# Shield.net
KiCad netlist of a schematic drawn in EAGLE
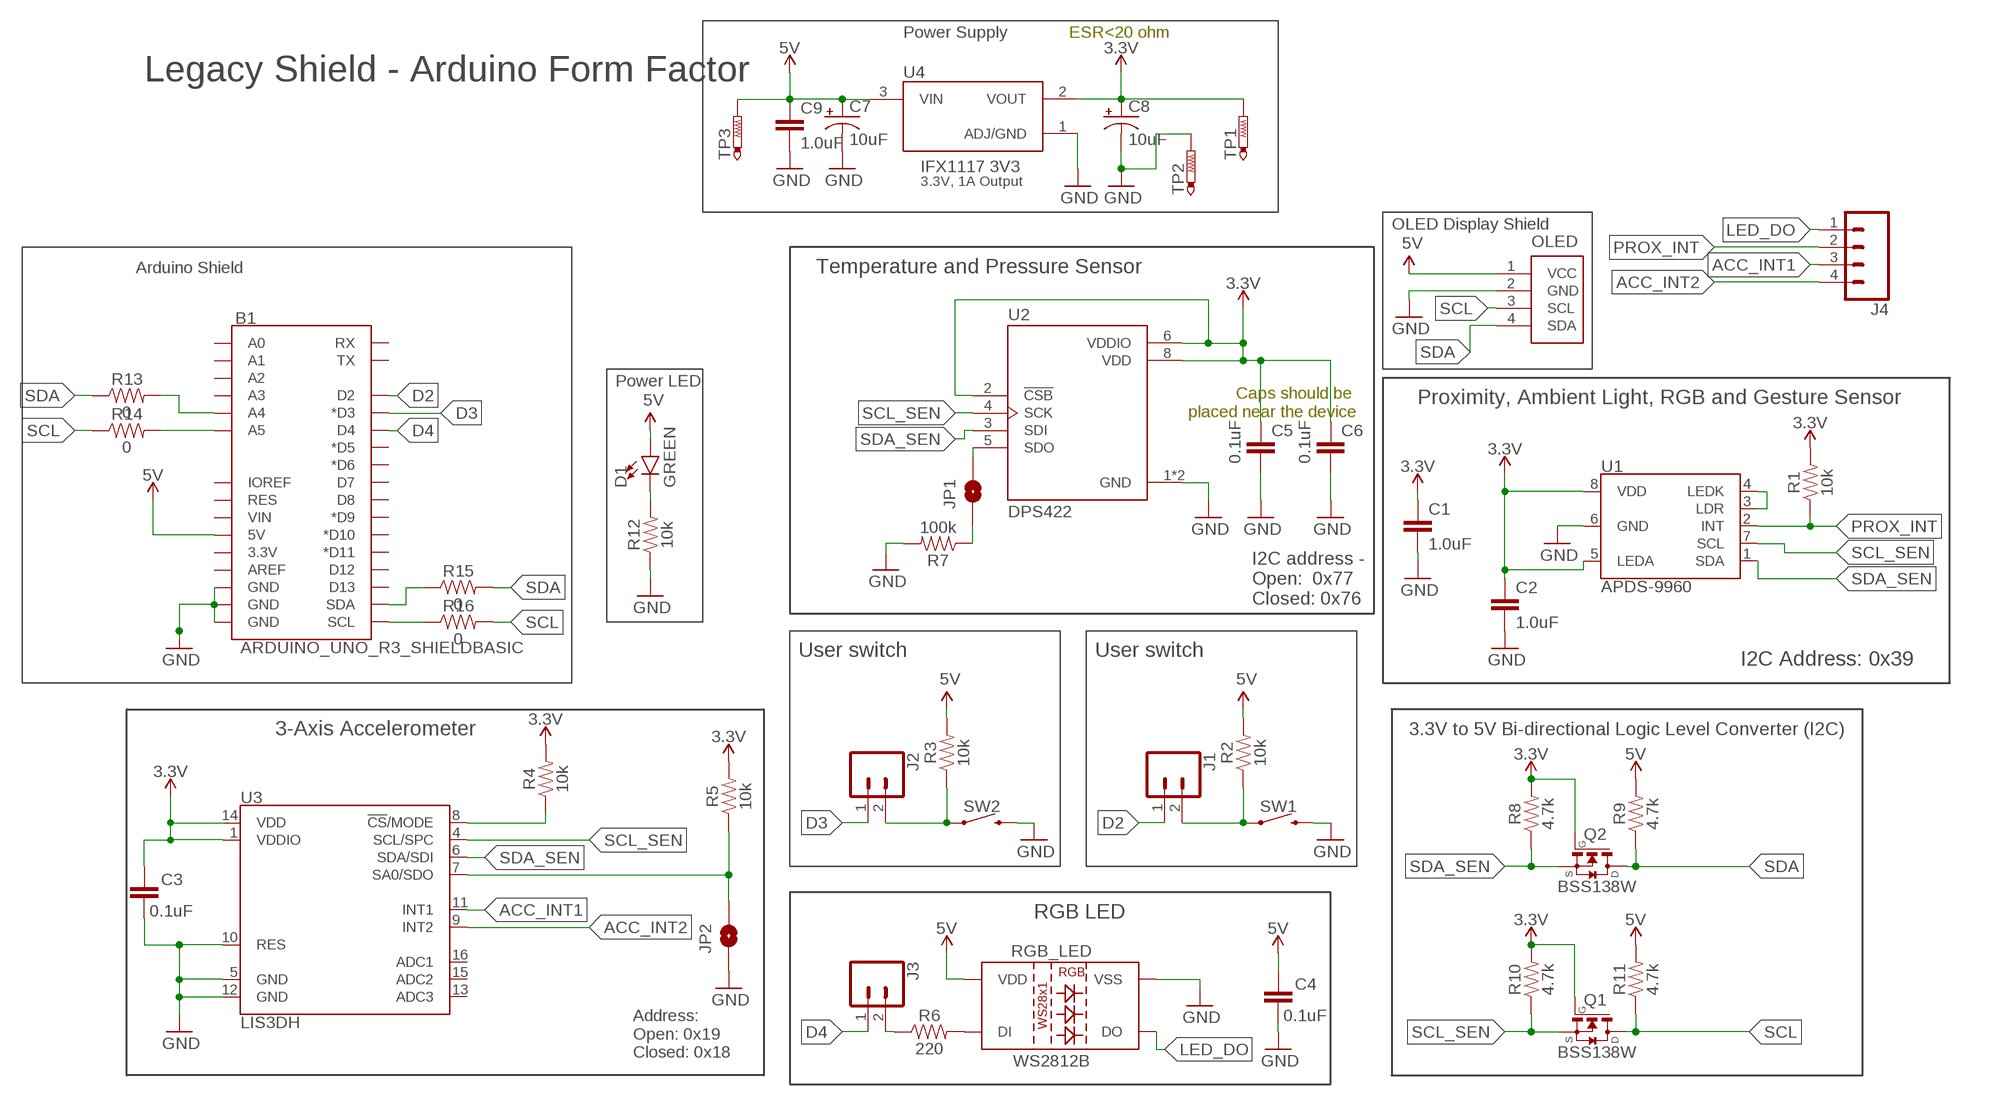
[diagram p0: schematic, sheet 1]

(export (version "E")
  (design (tool "Eeschema 10.0.6"))
  (components
    (comp (ref "B1")
      (value "ARDUINO_UNO_R3_SHIELDBASIC")
      (footprint "eagle-import:UNO_R3_SHIELD")
      (libsource (lib "eagle-import") (part "ARDUINO_UNO_R3_SHIELDBASIC"))
    )
    (comp (ref "C1")
      (value "1.0uF")
      (footprint "eagle-import:0603-CAP")
      (libsource (lib "eagle-import") (part "1.0UF-16V-10%(0603)"))
    )
    (comp (ref "C2")
      (value "1.0uF")
      (footprint "eagle-import:0603-CAP")
      (libsource (lib "eagle-import") (part "1.0UF-16V-10%(0603)"))
    )
    (comp (ref "C3")
      (value "0.1uF")
      (footprint "eagle-import:0603")
      (libsource (lib "eagle-import") (part "0.1UF-0603-25V-(+80/-20%)"))
    )
    (comp (ref "C4")
      (value "0.1uF")
      (footprint "eagle-import:0603")
      (libsource (lib "eagle-import") (part "0.1UF-0603-25V-(+80/-20%)"))
    )
    (comp (ref "C5")
      (value "0.1uF")
      (footprint "eagle-import:0603")
      (libsource (lib "eagle-import") (part "0.1UF-0603-25V-(+80/-20%)"))
    )
    (comp (ref "C6")
      (value "0.1uF")
      (footprint "eagle-import:0603")
      (libsource (lib "eagle-import") (part "0.1UF-0603-25V-(+80/-20%)"))
    )
    (comp (ref "C7")
      (value "10uF")
      (footprint "eagle-import:EIA3528")
      (libsource (lib "eagle-import") (part "10UF-POLAR-EIA3528-20V-10%(TANT)"))
    )
    (comp (ref "C8")
      (value "10uF")
      (footprint "eagle-import:EIA3528")
      (libsource (lib "eagle-import") (part "10UF-POLAR-EIA3528-20V-10%(TANT)"))
    )
    (comp (ref "C9")
      (value "1.0uF")
      (footprint "eagle-import:0603-CAP")
      (libsource (lib "eagle-import") (part "1.0UF-16V-10%(0603)"))
    )
    (comp (ref "D1")
      (value "GREEN")
      (footprint "eagle-import:LED-1206")
      (libsource (lib "eagle-import") (part "LED-GREEN1206"))
    )
    (comp (ref "J1")
      (value "CONN_02")
      (footprint "eagle-import:1X02")
      (libsource (lib "eagle-import") (part "CONN_02"))
    )
    (comp (ref "J2")
      (value "CONN_02")
      (footprint "eagle-import:1X02")
      (libsource (lib "eagle-import") (part "CONN_02"))
    )
    (comp (ref "J3")
      (value "CONN_02")
      (footprint "eagle-import:1X02")
      (libsource (lib "eagle-import") (part "CONN_02"))
    )
    (comp (ref "J4")
      (value "CONN_04")
      (footprint "eagle-import:1X04")
      (libsource (lib "eagle-import") (part "CONN_04"))
    )
    (comp (ref "JP1")
      (value "JUMPER-SMT_2_NO_SILK")
      (footprint "eagle-import:SMT-JUMPER_2_NO_SILK")
      (libsource (lib "eagle-import") (part "JUMPER-SMT_2_NO_SILK"))
    )
    (comp (ref "JP2")
      (value "JUMPER-SMT_2_NO_SILK")
      (footprint "eagle-import:SMT-JUMPER_2_NO_SILK")
      (libsource (lib "eagle-import") (part "JUMPER-SMT_2_NO_SILK"))
    )
    (comp (ref "OLED")
      (value "OLED_4_PIN")
      (footprint "eagle-import:OLED_4PIN")
      (description "0.96 Inch I2C/IIC 4pin OLED Display Module")
      (fields (field (name "MF") "Adafruit Industries"))
      (libsource (lib "eagle-import") (part "OLED_4_PIN"))
    )
    (comp (ref "Q1")
      (value "BSS138W")
      (footprint "eagle-import:SOT323-R")
      (description "N-Channel 60V 280mA (Ta) 500mW (Ta) Surface Mount PG-SOT323-3")
      (fields
        (field (name "DIGI-KEY_PART_NUMBER") "BSS138WCT-ND")
        (field (name "MF") "ON Semiconductor")
        (field (name "DIGI-KEY_PART_NUMBER_1") "BSS138WH6327XTSA1CT-ND")
        (field (name "DIGI-KEY_PURCHASE_URL") "https://www.digikey.in/product-detail/en/infineon-technologies/BSS138WH6327XTSA1/BSS138WH6327XTSA1CT-ND/5410000")
        (field (name "MF_1") "Infineon Technologies")
        (field (name "PACKAGE") "SOT-323")
      )
      (libsource (lib "eagle-import") (part "BSS138W"))
    )
    (comp (ref "Q2")
      (value "BSS138W")
      (footprint "eagle-import:SOT323-R")
      (description "N-Channel 60V 280mA (Ta) 500mW (Ta) Surface Mount PG-SOT323-3")
      (fields
        (field (name "DIGI-KEY_PART_NUMBER") "BSS138WCT-ND")
        (field (name "MF") "ON Semiconductor")
        (field (name "DIGI-KEY_PART_NUMBER_1") "BSS138WH6327XTSA1CT-ND")
        (field (name "DIGI-KEY_PURCHASE_URL") "https://www.digikey.in/product-detail/en/infineon-technologies/BSS138WH6327XTSA1/BSS138WH6327XTSA1CT-ND/5410000")
        (field (name "MF_1") "Infineon Technologies")
        (field (name "PACKAGE") "SOT-323")
      )
      (libsource (lib "eagle-import") (part "BSS138W"))
    )
    (comp (ref "R1")
      (value "10k")
      (footprint "eagle-import:0603")
      (libsource (lib "eagle-import") (part "10KOHM-0603-1/10W-1%"))
    )
    (comp (ref "R2")
      (value "10k")
      (footprint "eagle-import:0603")
      (libsource (lib "eagle-import") (part "10KOHM-0603-1/10W-1%"))
    )
    (comp (ref "R3")
      (value "10k")
      (footprint "eagle-import:0603")
      (libsource (lib "eagle-import") (part "10KOHM-0603-1/10W-1%"))
    )
    (comp (ref "R4")
      (value "10k")
      (footprint "eagle-import:0603")
      (libsource (lib "eagle-import") (part "10KOHM-0603-1/10W-1%"))
    )
    (comp (ref "R5")
      (value "10k")
      (footprint "eagle-import:0603")
      (libsource (lib "eagle-import") (part "10KOHM-0603-1/10W-1%"))
    )
    (comp (ref "R6")
      (value "220")
      (footprint "eagle-import:0603")
      (libsource (lib "eagle-import") (part "220OHM-0603-1/10W-1%"))
    )
    (comp (ref "R7")
      (value "100k")
      (footprint "eagle-import:0603")
      (libsource (lib "eagle-import") (part "100KOHM-0603-1/10W-1%"))
    )
    (comp (ref "R8")
      (value "4.7k")
      (footprint "eagle-import:0603")
      (libsource (lib "eagle-import") (part "4.7KOHM-0603-1/10W-1%"))
    )
    (comp (ref "R9")
      (value "4.7k")
      (footprint "eagle-import:0603")
      (libsource (lib "eagle-import") (part "4.7KOHM-0603-1/10W-1%"))
    )
    (comp (ref "R10")
      (value "4.7k")
      (footprint "eagle-import:0603")
      (libsource (lib "eagle-import") (part "4.7KOHM-0603-1/10W-1%"))
    )
    (comp (ref "R11")
      (value "4.7k")
      (footprint "eagle-import:0603")
      (libsource (lib "eagle-import") (part "4.7KOHM-0603-1/10W-1%"))
    )
    (comp (ref "R12")
      (value "10k")
      (footprint "eagle-import:0603")
      (libsource (lib "eagle-import") (part "10KOHM-0603-1/10W-1%"))
    )
    (comp (ref "R13")
      (value "0")
      (footprint "eagle-import:0603")
      (libsource (lib "eagle-import") (part "0OHM-0603-1/10W-5%"))
    )
    (comp (ref "R14")
      (value "0")
      (footprint "eagle-import:0603")
      (libsource (lib "eagle-import") (part "0OHM-0603-1/10W-5%"))
    )
    (comp (ref "R15")
      (value "0")
      (footprint "eagle-import:0603")
      (libsource (lib "eagle-import") (part "0OHM-0603-1/10W-5%"))
    )
    (comp (ref "R16")
      (value "0")
      (footprint "eagle-import:0603")
      (libsource (lib "eagle-import") (part "0OHM-0603-1/10W-5%"))
    )
    (comp (ref "RGB_LED")
      (value "WS2812B")
      (footprint "eagle-import:WS2812B")
      (libsource (lib "eagle-import") (part "WS2812B"))
    )
    (comp (ref "SW1")
      (value "MOMENTARY-SWITCH-SPST-PTH-6.0MM")
      (footprint "eagle-import:TACTILE_SWITCH_PTH_6.0MM")
      (libsource (lib "eagle-import") (part "MOMENTARY-SWITCH-SPST-PTH-6.0MM"))
    )
    (comp (ref "SW2")
      (value "MOMENTARY-SWITCH-SPST-PTH-6.0MM")
      (footprint "eagle-import:TACTILE_SWITCH_PTH_6.0MM")
      (libsource (lib "eagle-import") (part "MOMENTARY-SWITCH-SPST-PTH-6.0MM"))
    )
    (comp (ref "TP1")
      (value "PTR1TP08R")
      (footprint "eagle-import:TP08R")
      (libsource (lib "eagle-import") (part "PTR1TP08R"))
    )
    (comp (ref "TP2")
      (value "PTR1TP08R")
      (footprint "eagle-import:TP08R")
      (libsource (lib "eagle-import") (part "PTR1TP08R"))
    )
    (comp (ref "TP3")
      (value "PTR1TP08R")
      (footprint "eagle-import:TP08R")
      (libsource (lib "eagle-import") (part "PTR1TP08R"))
    )
    (comp (ref "U1")
      (value "APDS-9960")
      (footprint "eagle-import:APDS-9960")
      (fields (field (name "MF") "Broadcom Limited") (field (name "DIGI-KEY_PART_NUMBER") "516-3480-1-ND"))
      (libsource (lib "eagle-import") (part "APDS-9960"))
    )
    (comp (ref "U2")
      (value "DPS422")
      (footprint "eagle-import:XDCR_DPS422")
      (fields
        (field (name "MF") "Infineon Technologies")
        (field (name "DIGI-KEY_PART_NUMBER") "DPS422XTSA1CT-ND")
      )
      (libsource (lib "eagle-import") (part "DPS422"))
    )
    (comp (ref "U3")
      (value "LIS3DH")
      (footprint "eagle-import:LGA-16-3X3")
      (libsource (lib "eagle-import") (part "LIS3DH"))
    )
    (comp (ref "U4")
      (value "IFX1117 3V3")
      (footprint "eagle-import:SOT229P700X180-4N")
      (description "IC REG LINEAR 3.3V 1A SOT223-4")
      (fields
        (field (name "MF") "Advanced Monolithic Systems")
        (field (name "MP") "AMS1117-3.3")
        (field (name "DIGI-KEY_PART_NUMBER") "IFX1117MEV33HTMA1CT-ND")
        (field (name "MF_1") "Infineon Technologies")
        (field (name "MP_1") "IFX1117")
        (field (name "PACKAGE") "SOT223-4")
      )
      (libsource (lib "eagle-import") (part "AMS1117-3.3"))
    )
  )
  (nets
    (net (code "1") (name "3.3V") (class "Default")
      (node (ref "C1") (pin "1") (pinfunction "1_1") (pintype "passive"))
      (node (ref "C2") (pin "1") (pinfunction "1_1") (pintype "passive"))
      (node (ref "C3") (pin "1") (pinfunction "1_1") (pintype "passive"))
      (node (ref "C5") (pin "1") (pinfunction "1_1") (pintype "passive"))
      (node (ref "C6") (pin "1") (pinfunction "1_1") (pintype "passive"))
      (node (ref "C8") (pin "A") (pinfunction "+_A") (pintype "passive"))
      (node (ref "Q1") (pin "1") (pinfunction "G_1") (pintype "passive"))
      (node (ref "Q2") (pin "1") (pinfunction "G_1") (pintype "passive"))
      (node (ref "R1") (pin "2") (pinfunction "2_2") (pintype "passive"))
      (node (ref "R10") (pin "2") (pinfunction "2_2") (pintype "passive"))
      (node (ref "R4") (pin "2") (pinfunction "2_2") (pintype "passive"))
      (node (ref "R5") (pin "2") (pinfunction "2_2") (pintype "passive"))
      (node (ref "R8") (pin "2") (pinfunction "2_2") (pintype "passive"))
      (node (ref "TP1") (pin "TP") (pinfunction "TP_TP") (pintype "input"))
      (node (ref "U1") (pin "5") (pinfunction "LEDA_5") (pintype "bidirectional"))
      (node (ref "U1") (pin "8") (pinfunction "VDD_8") (pintype "bidirectional"))
      (node (ref "U2") (pin "2") (pinfunction "~{CSB}_2") (pintype "input"))
      (node (ref "U2") (pin "6") (pinfunction "VDDIO_6") (pintype "power_in"))
      (node (ref "U2") (pin "8") (pinfunction "VDD_8") (pintype "power_in"))
      (node (ref "U3") (pin "1") (pinfunction "VDDIO_1") (pintype "bidirectional"))
      (node (ref "U3") (pin "14") (pinfunction "VDD_14") (pintype "bidirectional"))
      (node (ref "U4") (pin "2") (pinfunction "VOUT_2") (pintype "output"))
    )
    (net (code "2") (name "5V") (class "Default")
      (node (ref "B1") (pin "5V") (pinfunction "5V_5V") (pintype "bidirectional"))
      (node (ref "C4") (pin "1") (pinfunction "1_1") (pintype "passive"))
      (node (ref "C7") (pin "A") (pinfunction "+_A") (pintype "passive"))
      (node (ref "C9") (pin "1") (pinfunction "1_1") (pintype "passive"))
      (node (ref "D1") (pin "A") (pinfunction "A_A") (pintype "passive"))
      (node (ref "OLED") (pin "1") (pinfunction "VCC_1") (pintype "bidirectional"))
      (node (ref "R11") (pin "2") (pinfunction "2_2") (pintype "passive"))
      (node (ref "R2") (pin "2") (pinfunction "2_2") (pintype "passive"))
      (node (ref "R3") (pin "2") (pinfunction "2_2") (pintype "passive"))
      (node (ref "R9") (pin "2") (pinfunction "2_2") (pintype "passive"))
      (node (ref "RGB_LED") (pin "1") (pinfunction "VDD_1") (pintype "bidirectional"))
      (node (ref "TP3") (pin "TP") (pinfunction "TP_TP") (pintype "input"))
      (node (ref "U4") (pin "3") (pinfunction "VIN_3") (pintype "input"))
    )
    (net (code "3") (name "ACC_INT1") (class "Default")
      (node (ref "J4") (pin "3") (pinfunction "3_3") (pintype "passive"))
      (node (ref "U3") (pin "11") (pinfunction "INT1_11") (pintype "bidirectional"))
    )
    (net (code "4") (name "ACC_INT2") (class "Default")
      (node (ref "J4") (pin "4") (pinfunction "4_4") (pintype "passive"))
      (node (ref "U3") (pin "9") (pinfunction "INT2_9") (pintype "bidirectional"))
    )
    (net (code "5") (name "D2") (class "Default")
      (node (ref "B1") (pin "D2") (pinfunction "D2_D2") (pintype "bidirectional"))
      (node (ref "J1") (pin "1") (pinfunction "1_1") (pintype "passive"))
    )
    (net (code "6") (name "D3") (class "Default")
      (node (ref "B1") (pin "D3") (pinfunction "*D3_D3") (pintype "bidirectional"))
      (node (ref "J2") (pin "1") (pinfunction "1_1") (pintype "passive"))
    )
    (net (code "7") (name "D4") (class "Default")
      (node (ref "B1") (pin "D4") (pinfunction "D4_D4") (pintype "bidirectional"))
      (node (ref "J3") (pin "1") (pinfunction "1_1") (pintype "passive"))
    )
    (net (code "8") (name "GND") (class "Default")
      (node (ref "B1") (pin "GND@0") (pinfunction "GND_GND@0") (pintype "bidirectional"))
      (node (ref "B1") (pin "GND@1") (pinfunction "GND_GND@1") (pintype "bidirectional"))
      (node (ref "B1") (pin "GND@2") (pinfunction "GND_GND@2") (pintype "bidirectional"))
      (node (ref "C1") (pin "2") (pinfunction "2_2") (pintype "passive"))
      (node (ref "C2") (pin "2") (pinfunction "2_2") (pintype "passive"))
      (node (ref "C3") (pin "2") (pinfunction "2_2") (pintype "passive"))
      (node (ref "C4") (pin "2") (pinfunction "2_2") (pintype "passive"))
      (node (ref "C5") (pin "2") (pinfunction "2_2") (pintype "passive"))
      (node (ref "C6") (pin "2") (pinfunction "2_2") (pintype "passive"))
      (node (ref "C7") (pin "C") (pinfunction "-_C") (pintype "passive"))
      (node (ref "C8") (pin "C") (pinfunction "-_C") (pintype "passive"))
      (node (ref "C9") (pin "2") (pinfunction "2_2") (pintype "passive"))
      (node (ref "JP2") (pin "1") (pinfunction "1_1") (pintype "passive"))
      (node (ref "OLED") (pin "2") (pinfunction "GND_2") (pintype "bidirectional"))
      (node (ref "R12") (pin "1") (pinfunction "1_1") (pintype "passive"))
      (node (ref "R7") (pin "2") (pinfunction "2_2") (pintype "passive"))
      (node (ref "RGB_LED") (pin "3") (pinfunction "VSS_3") (pintype "bidirectional"))
      (node (ref "SW1") (pin "3") (pinfunction "2_3") (pintype "passive"))
      (node (ref "SW2") (pin "3") (pinfunction "2_3") (pintype "passive"))
      (node (ref "TP2") (pin "TP") (pinfunction "TP_TP") (pintype "input"))
      (node (ref "U1") (pin "6") (pinfunction "GND_6") (pintype "bidirectional"))
      (node (ref "U2") (pin "1") (pinfunction "GND_1") (pintype "power_in"))
      (node (ref "U2") (pin "7") (pinfunction "GND_7") (pintype "power_in"))
      (node (ref "U3") (pin "10") (pinfunction "RES_10") (pintype "bidirectional"))
      (node (ref "U3") (pin "12") (pinfunction "GND_12") (pintype "bidirectional"))
      (node (ref "U3") (pin "5") (pinfunction "GND_5") (pintype "bidirectional"))
      (node (ref "U4") (pin "1") (pinfunction "ADJ/GND_1") (pintype "power_in"))
    )
    (net (code "9") (name "LED_DO") (class "Default")
      (node (ref "J4") (pin "1") (pinfunction "1_1") (pintype "passive"))
      (node (ref "RGB_LED") (pin "2") (pinfunction "DO_2") (pintype "bidirectional"))
    )
    (net (code "10") (name "Net-(B1-PadA4)") (class "Default")
      (node (ref "B1") (pin "A4") (pinfunction "A4_A4") (pintype "bidirectional"))
      (node (ref "R13") (pin "2") (pinfunction "2_2") (pintype "passive"))
    )
    (net (code "11") (name "Net-(B1-PadA5)") (class "Default")
      (node (ref "B1") (pin "A5") (pinfunction "A5_A5") (pintype "bidirectional"))
      (node (ref "R14") (pin "2") (pinfunction "2_2") (pintype "passive"))
    )
    (net (code "12") (name "Net-(B1-PadSCL)") (class "Default")
      (node (ref "B1") (pin "SCL") (pinfunction "SCL_SCL") (pintype "bidirectional"))
      (node (ref "R16") (pin "1") (pinfunction "1_1") (pintype "passive"))
    )
    (net (code "13") (name "Net-(B1-PadSDA)") (class "Default")
      (node (ref "B1") (pin "SDA") (pinfunction "SDA_SDA") (pintype "bidirectional"))
      (node (ref "R15") (pin "1") (pinfunction "1_1") (pintype "passive"))
    )
    (net (code "14") (name "Net-(D1-PadC)") (class "Default")
      (node (ref "D1") (pin "C") (pinfunction "C_C") (pintype "passive"))
      (node (ref "R12") (pin "2") (pinfunction "2_2") (pintype "passive"))
    )
    (net (code "15") (name "Net-(J1-Pad2)") (class "Default")
      (node (ref "J1") (pin "2") (pinfunction "2_2") (pintype "passive"))
      (node (ref "R2") (pin "1") (pinfunction "1_1") (pintype "passive"))
      (node (ref "SW1") (pin "1") (pinfunction "1_1") (pintype "passive"))
    )
    (net (code "16") (name "Net-(J2-Pad2)") (class "Default")
      (node (ref "J2") (pin "2") (pinfunction "2_2") (pintype "passive"))
      (node (ref "R3") (pin "1") (pinfunction "1_1") (pintype "passive"))
      (node (ref "SW2") (pin "1") (pinfunction "1_1") (pintype "passive"))
    )
    (net (code "17") (name "Net-(J3-Pad2)") (class "Default")
      (node (ref "J3") (pin "2") (pinfunction "2_2") (pintype "passive"))
      (node (ref "R6") (pin "1") (pinfunction "1_1") (pintype "passive"))
    )
    (net (code "18") (name "Net-(JP1-Pad1)") (class "Default")
      (node (ref "JP1") (pin "1") (pinfunction "1_1") (pintype "passive"))
      (node (ref "R7") (pin "1") (pinfunction "1_1") (pintype "passive"))
    )
    (net (code "19") (name "Net-(RGB_LED-DI)") (class "Default")
      (node (ref "R6") (pin "2") (pinfunction "2_2") (pintype "passive"))
      (node (ref "RGB_LED") (pin "4") (pinfunction "DI_4") (pintype "bidirectional"))
    )
    (net (code "20") (name "Net-(U1-LDR)") (class "Default")
      (node (ref "U1") (pin "3") (pinfunction "LDR_3") (pintype "bidirectional"))
      (node (ref "U1") (pin "4") (pinfunction "LEDK_4") (pintype "bidirectional"))
    )
    (net (code "21") (name "Net-(U2-SDO)") (class "Default")
      (node (ref "JP1") (pin "2") (pinfunction "2_2") (pintype "passive"))
      (node (ref "U2") (pin "5") (pinfunction "SDO_5") (pintype "output"))
    )
    (net (code "22") (name "Net-(U3-SA0{slash}SDO)") (class "Default")
      (node (ref "JP2") (pin "2") (pinfunction "2_2") (pintype "passive"))
      (node (ref "R5") (pin "1") (pinfunction "1_1") (pintype "passive"))
      (node (ref "U3") (pin "7") (pinfunction "SA0/SDO_7") (pintype "bidirectional"))
    )
    (net (code "23") (name "Net-(U3-~{CS}{slash}MODE)") (class "Default")
      (node (ref "R4") (pin "1") (pinfunction "1_1") (pintype "passive"))
      (node (ref "U3") (pin "8") (pinfunction "~{CS}/MODE_8") (pintype "bidirectional"))
    )
    (net (code "24") (name "PROX_INT") (class "Default")
      (node (ref "J4") (pin "2") (pinfunction "2_2") (pintype "passive"))
      (node (ref "R1") (pin "1") (pinfunction "1_1") (pintype "passive"))
      (node (ref "U1") (pin "2") (pinfunction "INT_2") (pintype "bidirectional"))
    )
    (net (code "25") (name "SCL") (class "Default")
      (node (ref "OLED") (pin "3") (pinfunction "SCL_3") (pintype "bidirectional"))
      (node (ref "Q1") (pin "3") (pinfunction "D_3") (pintype "passive"))
      (node (ref "R11") (pin "1") (pinfunction "1_1") (pintype "passive"))
      (node (ref "R14") (pin "1") (pinfunction "1_1") (pintype "passive"))
      (node (ref "R16") (pin "2") (pinfunction "2_2") (pintype "passive"))
    )
    (net (code "26") (name "SCL_SEN") (class "Default")
      (node (ref "Q1") (pin "2") (pinfunction "S_2") (pintype "passive"))
      (node (ref "R10") (pin "1") (pinfunction "1_1") (pintype "passive"))
      (node (ref "U1") (pin "7") (pinfunction "SCL_7") (pintype "bidirectional"))
      (node (ref "U2") (pin "4") (pinfunction "SCK_4") (pintype "input"))
      (node (ref "U3") (pin "4") (pinfunction "SCL/SPC_4") (pintype "bidirectional"))
    )
    (net (code "27") (name "SDA") (class "Default")
      (node (ref "OLED") (pin "4") (pinfunction "SDA_4") (pintype "bidirectional"))
      (node (ref "Q2") (pin "3") (pinfunction "D_3") (pintype "passive"))
      (node (ref "R13") (pin "1") (pinfunction "1_1") (pintype "passive"))
      (node (ref "R15") (pin "2") (pinfunction "2_2") (pintype "passive"))
      (node (ref "R9") (pin "1") (pinfunction "1_1") (pintype "passive"))
    )
    (net (code "28") (name "SDA_SEN") (class "Default")
      (node (ref "Q2") (pin "2") (pinfunction "S_2") (pintype "passive"))
      (node (ref "R8") (pin "1") (pinfunction "1_1") (pintype "passive"))
      (node (ref "U1") (pin "1") (pinfunction "SDA_1") (pintype "bidirectional"))
      (node (ref "U2") (pin "3") (pinfunction "SDI_3") (pintype "bidirectional"))
      (node (ref "U3") (pin "6") (pinfunction "SDA/SDI_6") (pintype "bidirectional"))
    )
    (net (code "29") (name "unconnected-(B1-*D5-PadD5)") (class "Default")
      (node (ref "B1") (pin "D5") (pinfunction "*D5_D5") (pintype "bidirectional"))
    )
    (net (code "30") (name "unconnected-(B1-*D6-PadD6)") (class "Default")
      (node (ref "B1") (pin "D6") (pinfunction "*D6_D6") (pintype "bidirectional"))
    )
    (net (code "31") (name "unconnected-(B1-*D9-PadD9)") (class "Default")
      (node (ref "B1") (pin "D9") (pinfunction "*D9_D9") (pintype "bidirectional"))
    )
    (net (code "32") (name "unconnected-(B1-*D10-PadD10)") (class "Default")
      (node (ref "B1") (pin "D10") (pinfunction "*D10_D10") (pintype "bidirectional"))
    )
    (net (code "33") (name "unconnected-(B1-*D11-PadD11)") (class "Default")
      (node (ref "B1") (pin "D11") (pinfunction "*D11_D11") (pintype "bidirectional"))
    )
    (net (code "34") (name "unconnected-(B1-Pad3.3V)") (class "Default")
      (node (ref "B1") (pin "3.3V") (pinfunction "3.3V_3.3V") (pintype "bidirectional"))
    )
    (net (code "35") (name "unconnected-(B1-PadA0)") (class "Default")
      (node (ref "B1") (pin "A0") (pinfunction "A0_A0") (pintype "bidirectional"))
    )
    (net (code "36") (name "unconnected-(B1-PadA1)") (class "Default")
      (node (ref "B1") (pin "A1") (pinfunction "A1_A1") (pintype "bidirectional"))
    )
    (net (code "37") (name "unconnected-(B1-PadA2)") (class "Default")
      (node (ref "B1") (pin "A2") (pinfunction "A2_A2") (pintype "bidirectional"))
    )
    (net (code "38") (name "unconnected-(B1-PadA3)") (class "Default")
      (node (ref "B1") (pin "A3") (pinfunction "A3_A3") (pintype "bidirectional"))
    )
    (net (code "39") (name "unconnected-(B1-PadAREF)") (class "Default")
      (node (ref "B1") (pin "AREF") (pinfunction "AREF_AREF") (pintype "bidirectional"))
    )
    (net (code "40") (name "unconnected-(B1-PadD7)") (class "Default")
      (node (ref "B1") (pin "D7") (pinfunction "D7_D7") (pintype "bidirectional"))
    )
    (net (code "41") (name "unconnected-(B1-PadD8)") (class "Default")
      (node (ref "B1") (pin "D8") (pinfunction "D8_D8") (pintype "bidirectional"))
    )
    (net (code "42") (name "unconnected-(B1-PadD12)") (class "Default")
      (node (ref "B1") (pin "D12") (pinfunction "D12_D12") (pintype "bidirectional"))
    )
    (net (code "43") (name "unconnected-(B1-PadD13)") (class "Default")
      (node (ref "B1") (pin "D13") (pinfunction "D13_D13") (pintype "bidirectional"))
    )
    (net (code "44") (name "unconnected-(B1-PadIOREF)") (class "Default")
      (node (ref "B1") (pin "IOREF") (pinfunction "IOREF_IOREF") (pintype "bidirectional"))
    )
    (net (code "45") (name "unconnected-(B1-PadRES)") (class "Default")
      (node (ref "B1") (pin "RES") (pinfunction "RES_RES") (pintype "bidirectional"))
    )
    (net (code "46") (name "unconnected-(B1-PadRX)") (class "Default")
      (node (ref "B1") (pin "RX") (pinfunction "RX_RX") (pintype "bidirectional"))
    )
    (net (code "47") (name "unconnected-(B1-PadTX)") (class "Default")
      (node (ref "B1") (pin "TX") (pinfunction "TX_TX") (pintype "bidirectional"))
    )
    (net (code "48") (name "unconnected-(B1-PadVIN)") (class "Default")
      (node (ref "B1") (pin "VIN") (pinfunction "VIN_VIN") (pintype "bidirectional"))
    )
    (net (code "49") (name "unconnected-(U3-ADC1-Pad16)") (class "Default")
      (node (ref "U3") (pin "16") (pinfunction "ADC1_16") (pintype "bidirectional"))
    )
    (net (code "50") (name "unconnected-(U3-ADC2-Pad15)") (class "Default")
      (node (ref "U3") (pin "15") (pinfunction "ADC2_15") (pintype "bidirectional"))
    )
    (net (code "51") (name "unconnected-(U3-ADC3-Pad13)") (class "Default")
      (node (ref "U3") (pin "13") (pinfunction "ADC3_13") (pintype "bidirectional"))
    )
  )
)
